# Sheet1.net
KiCad netlist of a schematic drawn in Altium Designer
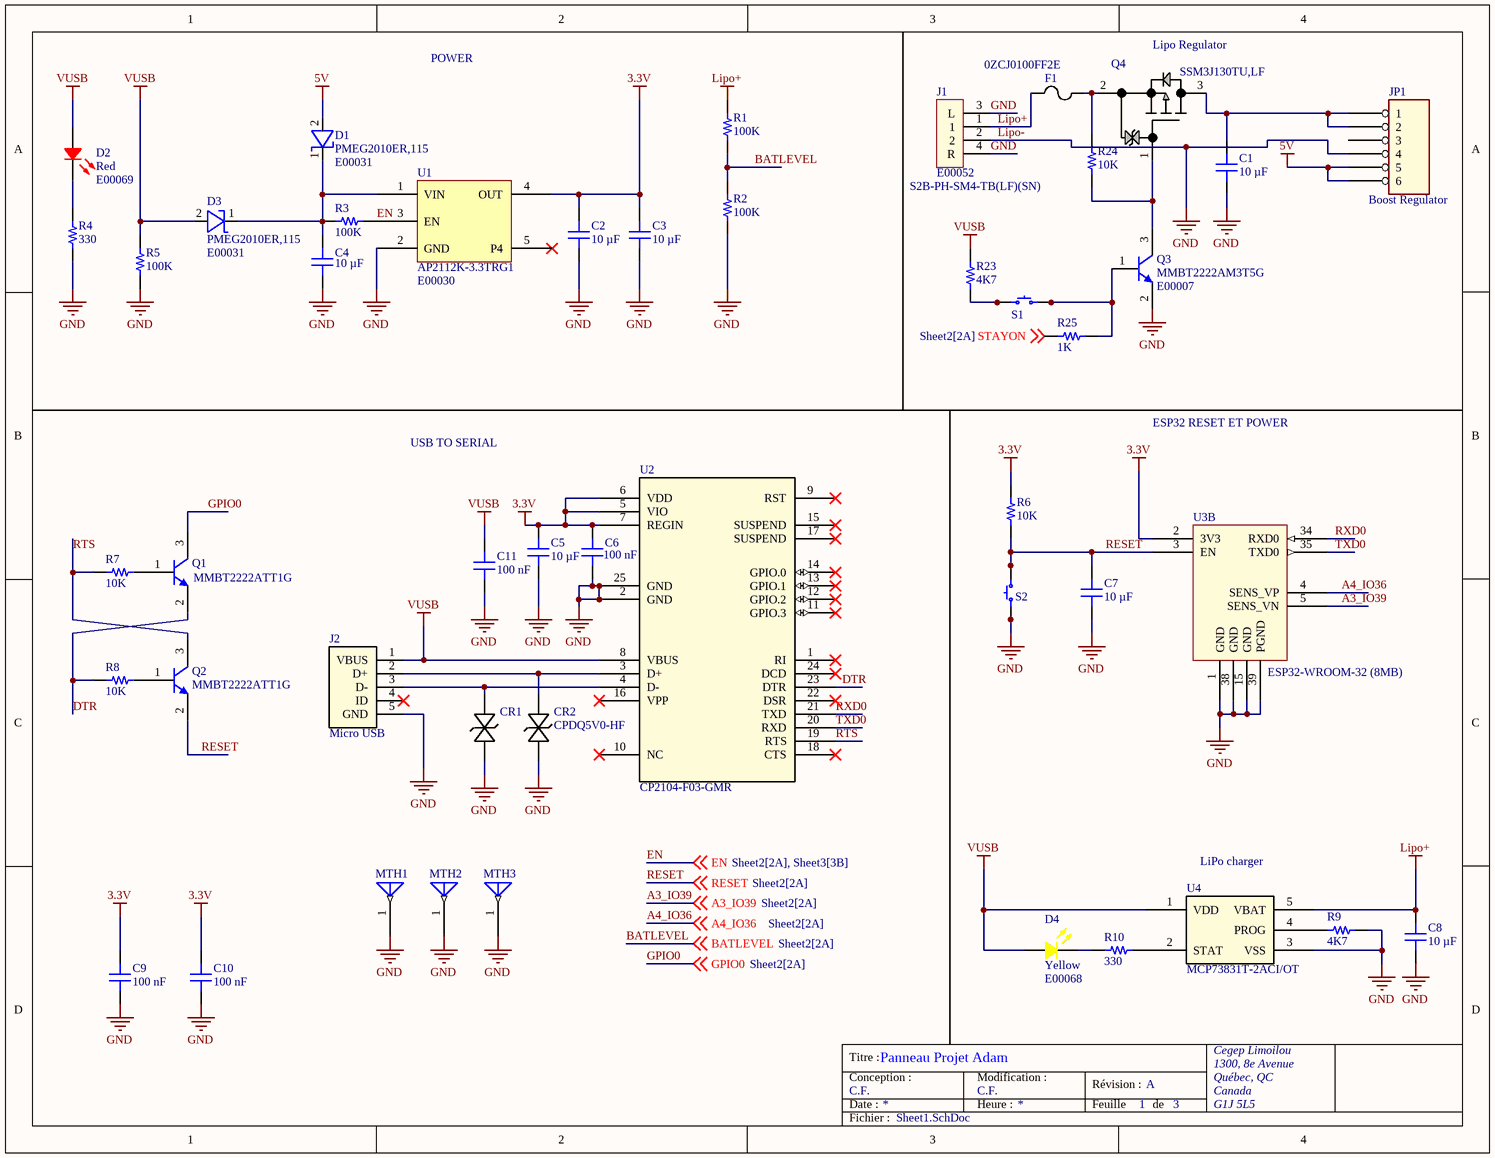
[diagram p0: Sheet1.SchDoc]

(export (version "E")
  (design (tool "Eeschema 10.0.6"))
  (components
    (comp (ref "C1")
      (value "10 µF")
      (footprint "CAP 0603")
      (description "CAP CER 10UF 10V X6S 0603")
      (fields
        (field (name "PART NUMBER") "GRM188C81A106MA73D")
        (field (name "MANUFACTURER") "Murata Electronics")
      )
      (libsource (lib "Celestial Altium Library - altium_library") (part "Capacitor"))
    )
    (comp (ref "C2")
      (value "10 µF")
      (footprint "CAP 0603")
      (description "CAP CER 10UF 10V X6S 0603")
      (fields
        (field (name "PART NUMBER") "GRM188C81A106MA73D")
        (field (name "MANUFACTURER") "Murata Electronics")
      )
      (libsource (lib "Celestial Altium Library - altium_library") (part "Capacitor"))
    )
    (comp (ref "C3")
      (value "10 µF")
      (footprint "CAP 0603")
      (description "CAP CER 10UF 10V X6S 0603")
      (fields
        (field (name "PART NUMBER") "GRM188C81A106MA73D")
        (field (name "MANUFACTURER") "Murata Electronics")
      )
      (libsource (lib "Celestial Altium Library - altium_library") (part "Capacitor"))
    )
    (comp (ref "C4")
      (value "10 µF")
      (footprint "CAP 0603")
      (description "CAP CER 10UF 10V X6S 0603")
      (fields
        (field (name "PART NUMBER") "GRM188C81A106MA73D")
        (field (name "MANUFACTURER") "Murata Electronics")
      )
      (libsource (lib "Celestial Altium Library - altium_library") (part "Capacitor"))
    )
    (comp (ref "C5")
      (value "10 µF")
      (footprint "CAP 0603")
      (description "CAP CER 10UF 10V X6S 0603")
      (fields
        (field (name "PART NUMBER") "GRM188C81A106MA73D")
        (field (name "MANUFACTURER") "Murata Electronics")
      )
      (libsource (lib "Celestial Altium Library - altium_library") (part "Capacitor"))
    )
    (comp (ref "C6")
      (value "100 nF")
      (footprint "CAP 0603")
      (description "CAP CER 10UF 10V X6S 0603")
      (fields
        (field (name "PART NUMBER") "GRM188C81A106MA73D")
        (field (name "MANUFACTURER") "Murata Electronics")
      )
      (libsource (lib "Celestial Altium Library - altium_library") (part "Capacitor"))
    )
    (comp (ref "C7")
      (value "10 µF")
      (footprint "CAP 0603")
      (description "CAP CER 10UF 10V X6S 0603")
      (fields
        (field (name "PART NUMBER") "GRM188C81A106MA73D")
        (field (name "MANUFACTURER") "Murata Electronics")
      )
      (libsource (lib "Celestial Altium Library - altium_library") (part "Capacitor"))
    )
    (comp (ref "C8")
      (value "10 µF")
      (footprint "CAP 0603")
      (description "CAP CER 10UF 10V X6S 0603")
      (fields
        (field (name "PART NUMBER") "GRM188C81A106MA73D")
        (field (name "MANUFACTURER") "Murata Electronics")
      )
      (libsource (lib "Celestial Altium Library - altium_library") (part "Capacitor"))
    )
    (comp (ref "C9")
      (value "100 nF")
      (footprint "CAP 0603")
      (description "CAP CER 10UF 10V X6S 0603")
      (fields
        (field (name "PART NUMBER") "GRM188C81A106MA73D")
        (field (name "MANUFACTURER") "Murata Electronics")
      )
      (libsource (lib "Celestial Altium Library - altium_library") (part "Capacitor"))
    )
    (comp (ref "C10")
      (value "100 nF")
      (footprint "CAP 0603")
      (description "CAP CER 10UF 10V X6S 0603")
      (fields
        (field (name "PART NUMBER") "GRM188C81A106MA73D")
        (field (name "MANUFACTURER") "Murata Electronics")
      )
      (libsource (lib "Celestial Altium Library - altium_library") (part "Capacitor"))
    )
    (comp (ref "C11")
      (value "100 nF")
      (footprint "CAP 0603")
      (description "CAP CER 10UF 10V X6S 0603")
      (fields
        (field (name "PART NUMBER") "GRM188C81A106MA73D")
        (field (name "MANUFACTURER") "Murata Electronics")
      )
      (libsource (lib "Celestial Altium Library - altium_library") (part "Capacitor"))
    )
    (comp (ref "CR1")
      (value "CPDQ5V0-HF")
      (footprint "CPDQ-M")
      (description "Diode TVS bidirectionnel")
      (libsource (lib "ADAM LIBRARY") (part "CPDQ5V0-HF"))
    )
    (comp (ref "CR2")
      (value "CPDQ5V0-HF")
      (footprint "CPDQ-M")
      (description "Diode TVS bidirectionnel")
      (libsource (lib "ADAM LIBRARY") (part "CPDQ5V0-HF"))
    )
    (comp (ref "D1")
      (value "PMEG2010ER,115")
      (footprint "DIODE_PMEG2010ER,115_NEX")
      (description "Diode shotkey")
      (fields (field (name "ADAM INVENTORY NUMBER 1") "E00031"))
      (libsource (lib "ADAM LIBRARY") (part "PMEG2010ER,115"))
    )
    (comp (ref "D2")
      (value "Red")
      (footprint "Red Led 0603")
      (description "0603 RED LED")
      (fields
        (field (name "MANUFACTURER") "American Bright Optoelectronics Corporation")
        (field (name "ADAM INVENTORY NUMBER 1") "E00069")
      )
      (libsource (lib "ADAM LIBRARY") (part "0603 RED LED"))
    )
    (comp (ref "D3")
      (value "PMEG2010ER,115")
      (footprint "DIODE_PMEG2010ER,115_NEX")
      (description "Diode shotkey")
      (fields (field (name "ADAM INVENTORY NUMBER 1") "E00031"))
      (libsource (lib "ADAM LIBRARY") (part "PMEG2010ER,115"))
    )
    (comp (ref "D4")
      (value "Yellow")
      (footprint "YELLOW LED 0603 - duplicate")
      (description "0603 YELLOW")
      (fields
        (field (name "MANUFACTURER") "American Bright Optoelectronics Corporation")
        (field (name "ADAM INVENTORY NUMBER 1") "E00068")
      )
      (libsource (lib "ADAM LIBRARY") (part "0603 YELLOW LED"))
    )
    (comp (ref "F1")
      (value "0ZCJ0100FF2E")
      (footprint "Fuse 500mA 0.6mm")
      (description "No Description Available")
      (libsource (lib "ADAM LIBRARY") (part "NANOSMDCH030F/24-02"))
    )
    (comp (ref "J1")
      (value "CONN JST 2P SM 90DEG")
      (footprint "S2B-PH-SM4-TB_LF__SN")
      (description "CONN SM JST 2P")
      (fields
        (field (name "ADAM INVENTORY NUMBER 1") "E00052")
        (field (name "SUPPLIER PART NUMBER 1") "S2B-PH-SM4-TB(LF)(SN)")
        (field (name "COPYRIGHT") "Copyright (C) 2023 Ultra Librarian. All rights reserved.")
      )
      (libsource (lib "ADAM LIBRARY") (part "CONN JST 2P SM 90DEG"))
    )
    (comp (ref "J2")
      (value "Micro USB")
      (footprint "CONN_1050170001_MOL")
      (description "No Description Available")
      (fields (field (name "COPYRIGHT") "Copyright (C) 2023 Ultra Librarian. All rights reserved."))
      (libsource (lib "Pannel") (part "1050170001"))
    )
    (comp (ref "JP1")
      (value "Boost Regulator")
      (footprint "HDR1X6")
      (libsource (lib "PCBDEV_Library") (part "HEADER 6"))
    )
    (comp (ref "MTH1")
      (value "NTENNA")
      (footprint "Mounting Hole")
      (libsource (lib "PCBDEV_Library") (part "ANTENNA"))
    )
    (comp (ref "MTH2")
      (value "ANTENNA")
      (footprint "Mounting Hole")
      (libsource (lib "PCBDEV_Library") (part "ANTENNA"))
    )
    (comp (ref "MTH3")
      (value "ANTENNA")
      (footprint "Mounting Hole")
      (libsource (lib "PCBDEV_Library") (part "ANTENNA"))
    )
    (comp (ref "Q1")
      (value "MMBT2222ATT1G")
      (footprint "SOT-416_1P65X0P9_ONS-M")
      (description "TRANS NPN 40V 0.6A SC75-3")
      (fields (field (name "MANUFACTURER") "ON Semiconductor"))
      (libsource (lib "Celestial Altium Library - altium_library") (part "ON SEMI NPN SC-75"))
    )
    (comp (ref "Q2")
      (value "MMBT2222ATT1G")
      (footprint "SOT-416_1P65X0P9_ONS-M")
      (description "TRANS NPN 40V 0.6A SC75-3")
      (fields (field (name "MANUFACTURER") "ON Semiconductor"))
      (libsource (lib "Celestial Altium Library - altium_library") (part "ON SEMI NPN SC-75"))
    )
    (comp (ref "Q3")
      (value "MMBT2222AM3T5G")
      (footprint "SOT_4C-E3-08_VIS-M")
      (description "TRANS NPN 40V 0.6A SOT-723")
      (fields
        (field (name "MANUFACTURER") "ON Semiconductor")
        (field (name "ADAM INVENTORY NUMBER 1") "E00007")
      )
      (libsource (lib "ADAM LIBRARY") (part "TRANS NPN 40V"))
    )
    (comp (ref "Q4")
      (value "SSM3J130TU,LF")
      (footprint "UFM_TOS")
      (description "No Description Available")
      (libsource (lib "ADAM LIBRARY") (part "SSM3J130TU,LF"))
    )
    (comp (ref "R1")
      (value "100K")
      (footprint "RES 0603")
      (description "RES SMD 100K OHM 0.1% 1/16W 0603")
      (fields
        (field (name "PART NUMBER") "CPF0603B100KE")
        (field (name "MANUFACTURER") "TE Connectivity Passive Product")
      )
      (libsource (lib "Celestial Altium Library - altium_library") (part "Resistor"))
    )
    (comp (ref "R2")
      (value "100K")
      (footprint "RES 0603")
      (description "RES SMD 100K OHM 0.1% 1/16W 0603")
      (fields
        (field (name "PART NUMBER") "CPF0603B100KE")
        (field (name "MANUFACTURER") "TE Connectivity Passive Product")
      )
      (libsource (lib "Celestial Altium Library - altium_library") (part "Resistor"))
    )
    (comp (ref "R3")
      (value "100K")
      (footprint "RES 0603")
      (description "RES SMD 100K OHM 0.1% 1/16W 0603")
      (fields
        (field (name "PART NUMBER") "CPF0603B100KE")
        (field (name "MANUFACTURER") "TE Connectivity Passive Product")
      )
      (libsource (lib "Celestial Altium Library - altium_library") (part "Resistor"))
    )
    (comp (ref "R4")
      (value "330")
      (footprint "RES 0603")
      (description "RES SMD 1K OHM 0.1% 1/16W 0603")
      (fields
        (field (name "PART NUMBER") "CPF0603B1K0E")
        (field (name "MANUFACTURER") "TE Connectivity Passive Product")
      )
      (libsource (lib "Celestial Altium Library - altium_library") (part "Resistor"))
    )
    (comp (ref "R5")
      (value "100K")
      (footprint "RES 0603")
      (description "RES SMD 100K OHM 0.1% 1/16W 0603")
      (fields
        (field (name "PART NUMBER") "CPF0603B100KE")
        (field (name "MANUFACTURER") "TE Connectivity Passive Product")
      )
      (libsource (lib "Celestial Altium Library - altium_library") (part "Resistor"))
    )
    (comp (ref "R6")
      (value "10K")
      (footprint "RES 0603")
      (description "RES 10K OHM 0.1% 1/16W 0603")
      (fields
        (field (name "PART NUMBER") "RNCS0603BKE10K0")
        (field (name "MANUFACTURER") "Stackpole Electronics Inc")
      )
      (libsource (lib "Celestial Altium Library - altium_library") (part "Resistor"))
    )
    (comp (ref "R7")
      (value "10K")
      (footprint "RES 0603")
      (description "RES 10K OHM 0.1% 1/16W 0603")
      (fields
        (field (name "PART NUMBER") "RNCS0603BKE10K0")
        (field (name "MANUFACTURER") "Stackpole Electronics Inc")
      )
      (libsource (lib "Celestial Altium Library - altium_library") (part "Resistor"))
    )
    (comp (ref "R8")
      (value "10K")
      (footprint "RES 0603")
      (description "RES 10K OHM 0.1% 1/16W 0603")
      (fields
        (field (name "PART NUMBER") "RNCS0603BKE10K0")
        (field (name "MANUFACTURER") "Stackpole Electronics Inc")
      )
      (libsource (lib "Celestial Altium Library - altium_library") (part "Resistor"))
    )
    (comp (ref "R9")
      (value "4K7")
      (footprint "RES 0603")
      (description "RES SMD 4.7K OHM 1% 1/10W 0603")
      (fields (field (name "PART NUMBER") "RT0603FRE074K7L") (field (name "MANUFACTURER") "Yageo"))
      (libsource (lib "Celestial Altium Library - altium_library") (part "Resistor"))
    )
    (comp (ref "R10")
      (value "330")
      (footprint "RES 0603")
      (description "RES SMD 1K OHM 0.1% 1/16W 0603")
      (fields
        (field (name "PART NUMBER") "CPF0603B1K0E")
        (field (name "MANUFACTURER") "TE Connectivity Passive Product")
      )
      (libsource (lib "Celestial Altium Library - altium_library") (part "Resistor"))
    )
    (comp (ref "R23")
      (value "4K7")
      (footprint "RES 0603")
      (description "RES SMD 100K OHM 0.1% 1/16W 0603")
      (fields
        (field (name "PART NUMBER") "CPF0603B100KE")
        (field (name "MANUFACTURER") "TE Connectivity Passive Product")
      )
      (libsource (lib "Celestial Altium Library - altium_library") (part "Resistor"))
    )
    (comp (ref "R24")
      (value "10K")
      (footprint "RES 0603")
      (description "RES SMD 100K OHM 0.1% 1/16W 0603")
      (fields
        (field (name "PART NUMBER") "CPF0603B100KE")
        (field (name "MANUFACTURER") "TE Connectivity Passive Product")
      )
      (libsource (lib "Celestial Altium Library - altium_library") (part "Resistor"))
    )
    (comp (ref "R25")
      (value "1K")
      (footprint "RES 0603")
      (description "RES SMD 100K OHM 0.1% 1/16W 0603")
      (fields
        (field (name "PART NUMBER") "CPF0603B100KE")
        (field (name "MANUFACTURER") "TE Connectivity Passive Product")
      )
      (libsource (lib "Celestial Altium Library - altium_library") (part "Resistor"))
    )
    (comp (ref "S1")
      (value "KMR741NG ULC LFS")
      (footprint "Switch Lin SMD")
      (description "SWITCH TACTILE SPST-NO 50MA 32V")
      (fields (field (name "MANUFACTURER") "C&K"))
      (libsource (lib "Celestial Altium Library - altium_library") (part "SPST-NO 4 PIN"))
    )
    (comp (ref "S2")
      (value "KMR741NG ULC LFS")
      (footprint "Switch Lin SMD")
      (description "SWITCH TACTILE SPST-NO 50MA 32V")
      (fields (field (name "MANUFACTURER") "C&K"))
      (libsource (lib "Celestial Altium Library - altium_library") (part "SPST-NO 4 PIN"))
    )
    (comp (ref "U1")
      (value "AP2112K-3.3TRG1")
      (footprint "AP2112R5-3.3TRG1_DIO")
      (description "REG LINEAIRE 3.3V")
      (fields (field (name "ADAM INVENTORY NUMBER 1") "E00030"))
      (libsource (lib "ADAM LIBRARY") (part "REG LIN 3.3V"))
    )
    (comp (ref "U2")
      (value "CP2104-F03-GMR")
      (footprint "QFN_F03-GMR_SIL-M")
      (description "No Description Available")
      (fields (field (name "COPYRIGHT") "Copyright (C) 2023 Ultra Librarian. All rights reserved."))
      (libsource (lib "Pannel") (part "CP2104-F03-GMR"))
    )
    (comp (ref "U3")
      (value "ESP32-WROOM-32 (8MB)")
      (footprint "ESP32-WROOM-32D")
      (description "No Description Available")
      (fields (field (name "COPYRIGHT") "Copyright (C) 2023 Ultra Librarian. All rights reserved."))
      (libsource (lib "ESP32-WROOM-32_8MB_") (part "ESP32-WROOM-32 (8MB)"))
    )
    (comp (ref "U4")
      (value "MCP73831T-2ACI/OT")
      (footprint "SOT23_MCP73831T-2ACI/OT_HNW")
      (description "No Description Available")
      (fields (field (name "COPYRIGHT") "Copyright (C) 2023 Ultra Librarian. All rights reserved."))
      (libsource (lib "Pannel") (part "MCP73831T-2ACI/OT"))
    )
  )
  (nets
    (net (code "1") (name "/DTR") (class "Default")
      (node (ref "Q1") (pin "2") (pinfunction "E_2") (pintype "passive"))
      (node (ref "R8") (pin "2") (pinfunction "2_2") (pintype "passive"))
      (node (ref "U2") (pin "23") (pinfunction "DTR_23") (pintype "passive"))
    )
    (net (code "2") (name "/RTS") (class "Default")
      (node (ref "Q2") (pin "3") (pinfunction "C_3") (pintype "passive"))
      (node (ref "R7") (pin "2") (pinfunction "2_2") (pintype "passive"))
      (node (ref "U2") (pin "19") (pinfunction "RTS_19") (pintype "passive"))
    )
    (net (code "3") (name "/RXD0") (class "Default")
      (node (ref "U2") (pin "21") (pinfunction "TXD_21") (pintype "passive"))
      (node (ref "U3") (pin "34") (pinfunction "RXD0_34") (pintype "input"))
    )
    (net (code "4") (name "/TXD0") (class "Default")
      (node (ref "U2") (pin "20") (pinfunction "RXD_20") (pintype "passive"))
      (node (ref "U3") (pin "35") (pinfunction "TXD0_35") (pintype "output"))
    )
    (net (code "5") (name "3.3V") (class "Default")
      (node (ref "C10") (pin "2") (pinfunction "2_2") (pintype "passive"))
      (node (ref "C2") (pin "2") (pinfunction "2_2") (pintype "passive"))
      (node (ref "C3") (pin "2") (pinfunction "2_2") (pintype "passive"))
      (node (ref "C5") (pin "2") (pinfunction "2_2") (pintype "passive"))
      (node (ref "C6") (pin "2") (pinfunction "2_2") (pintype "passive"))
      (node (ref "C9") (pin "2") (pinfunction "2_2") (pintype "passive"))
      (node (ref "R6") (pin "2") (pinfunction "2_2") (pintype "passive"))
      (node (ref "U1") (pin "4") (pinfunction "OUT_4") (pintype "passive"))
      (node (ref "U2") (pin "5") (pinfunction "VIO_5") (pintype "passive"))
      (node (ref "U2") (pin "6") (pinfunction "VDD_6") (pintype "power_in"))
      (node (ref "U2") (pin "7") (pinfunction "REGIN_7") (pintype "passive"))
      (node (ref "U3") (pin "2") (pinfunction "3V3_2") (pintype "power_in"))
    )
    (net (code "6") (name "5V") (class "Default")
      (node (ref "D1") (pin "2") (pinfunction "A_2") (pintype "passive"))
      (node (ref "JP1") (pin "5") (pinfunction "5_5") (pintype "passive"))
      (node (ref "JP1") (pin "6") (pinfunction "6_6") (pintype "passive"))
    )
    (net (code "7") (name "A3_IO39") (class "Default")
      (node (ref "U3") (pin "5") (pinfunction "SENS_VN_5") (pintype "passive"))
    )
    (net (code "8") (name "A4_IO36") (class "Default")
      (node (ref "U3") (pin "4") (pinfunction "SENS_VP_4") (pintype "passive"))
    )
    (net (code "9") (name "BATLEVEL") (class "Default")
      (node (ref "R1") (pin "1") (pinfunction "1_1") (pintype "passive"))
      (node (ref "R2") (pin "2") (pinfunction "2_2") (pintype "passive"))
    )
    (net (code "10") (name "EN") (class "Default")
      (node (ref "R3") (pin "1") (pinfunction "1_1") (pintype "passive"))
      (node (ref "U1") (pin "3") (pinfunction "EN_3") (pintype "passive"))
    )
    (net (code "11") (name "GND") (class "Default")
      (node (ref "C1") (pin "1") (pinfunction "1_1") (pintype "passive"))
      (node (ref "C10") (pin "1") (pinfunction "1_1") (pintype "passive"))
      (node (ref "C11") (pin "1") (pinfunction "1_1") (pintype "passive"))
      (node (ref "C2") (pin "1") (pinfunction "1_1") (pintype "passive"))
      (node (ref "C3") (pin "1") (pinfunction "1_1") (pintype "passive"))
      (node (ref "C4") (pin "1") (pinfunction "1_1") (pintype "passive"))
      (node (ref "C5") (pin "1") (pinfunction "1_1") (pintype "passive"))
      (node (ref "C6") (pin "1") (pinfunction "1_1") (pintype "passive"))
      (node (ref "C7") (pin "1") (pinfunction "1_1") (pintype "passive"))
      (node (ref "C8") (pin "1") (pinfunction "1_1") (pintype "passive"))
      (node (ref "C9") (pin "1") (pinfunction "1_1") (pintype "passive"))
      (node (ref "CR1") (pin "1") (pinfunction "1_1") (pintype "passive"))
      (node (ref "CR2") (pin "1") (pinfunction "1_1") (pintype "passive"))
      (node (ref "J1") (pin "2") (pinfunction "2_2") (pintype "passive"))
      (node (ref "J1") (pin "3") (pinfunction "L_3") (pintype "passive"))
      (node (ref "J1") (pin "4") (pinfunction "R_4") (pintype "passive"))
      (node (ref "J2") (pin "5") (pinfunction "GND_5") (pintype "passive"))
      (node (ref "JP1") (pin "4") (pinfunction "4_4") (pintype "passive"))
      (node (ref "MTH1") (pin "1") (pinfunction "1_1") (pintype "output"))
      (node (ref "MTH2") (pin "1") (pinfunction "1_1") (pintype "output"))
      (node (ref "MTH3") (pin "1") (pinfunction "1_1") (pintype "output"))
      (node (ref "Q3") (pin "2") (pinfunction "E_2") (pintype "passive"))
      (node (ref "R2") (pin "1") (pinfunction "1_1") (pintype "passive"))
      (node (ref "R4") (pin "2") (pinfunction "2_2") (pintype "passive"))
      (node (ref "R5") (pin "1") (pinfunction "1_1") (pintype "passive"))
      (node (ref "R9") (pin "2") (pinfunction "2_2") (pintype "passive"))
      (node (ref "S2") (pin "1") (pinfunction "1_1") (pintype "passive"))
      (node (ref "S2") (pin "2") (pinfunction "2_2") (pintype "passive"))
      (node (ref "U1") (pin "2") (pinfunction "GND_2") (pintype "passive"))
      (node (ref "U2") (pin "2") (pinfunction "GND_2") (pintype "passive"))
      (node (ref "U2") (pin "25") (pinfunction "GND_25") (pintype "passive"))
      (node (ref "U3") (pin "1") (pinfunction "GND_1") (pintype "power_in"))
      (node (ref "U3") (pin "15") (pinfunction "GND_15") (pintype "power_in"))
      (node (ref "U3") (pin "38") (pinfunction "GND_38") (pintype "power_in"))
      (node (ref "U3") (pin "39") (pinfunction "PGND_39") (pintype "power_in"))
      (node (ref "U4") (pin "3") (pinfunction "VSS_3") (pintype "passive"))
    )
    (net (code "12") (name "GPIO0") (class "Default")
      (node (ref "Q1") (pin "3") (pinfunction "C_3") (pintype "passive"))
    )
    (net (code "13") (name "Lipo+") (class "Default")
      (node (ref "C8") (pin "2") (pinfunction "2_2") (pintype "passive"))
      (node (ref "F1") (pin "1") (pinfunction "1_1") (pintype "passive"))
      (node (ref "J1") (pin "1") (pinfunction "1_1") (pintype "passive"))
      (node (ref "R1") (pin "2") (pinfunction "2_2") (pintype "passive"))
      (node (ref "U4") (pin "5") (pinfunction "VBAT_5") (pintype "passive"))
    )
    (net (code "14") (name "Net-(C1-Pad2)") (class "Default")
      (node (ref "C1") (pin "2") (pinfunction "2_2") (pintype "passive"))
      (node (ref "JP1") (pin "1") (pinfunction "1_1") (pintype "passive"))
      (node (ref "JP1") (pin "2") (pinfunction "2_2") (pintype "passive"))
      (node (ref "Q4") (pin "3") (pinfunction "3_3") (pintype "passive"))
    )
    (net (code "15") (name "Net-(D1-K)") (class "Default")
      (node (ref "C4") (pin "2") (pinfunction "2_2") (pintype "passive"))
      (node (ref "D1") (pin "1") (pinfunction "K_1") (pintype "passive"))
      (node (ref "D3") (pin "1") (pinfunction "K_1") (pintype "passive"))
      (node (ref "R3") (pin "2") (pinfunction "2_2") (pintype "passive"))
      (node (ref "U1") (pin "1") (pinfunction "VIN_1") (pintype "passive"))
    )
    (net (code "16") (name "Net-(D2-Pad2)") (class "Default")
      (node (ref "D2") (pin "2") (pinfunction "2_2") (pintype "passive"))
      (node (ref "R4") (pin "1") (pinfunction "1_1") (pintype "passive"))
    )
    (net (code "17") (name "Net-(D4-Pad2)") (class "Default")
      (node (ref "D4") (pin "2") (pinfunction "2_2") (pintype "passive"))
      (node (ref "R10") (pin "1") (pinfunction "1_1") (pintype "passive"))
    )
    (net (code "18") (name "Net-(F1-Pad2)") (class "Default")
      (node (ref "F1") (pin "2") (pinfunction "2_2") (pintype "passive"))
      (node (ref "Q4") (pin "2") (pinfunction "2_2") (pintype "passive"))
      (node (ref "R24") (pin "2") (pinfunction "2_2") (pintype "passive"))
    )
    (net (code "19") (name "Net-(J2-D+)") (class "Default")
      (node (ref "CR2") (pin "2") (pinfunction "2_2") (pintype "passive"))
      (node (ref "J2") (pin "2") (pinfunction "D+_2") (pintype "passive"))
      (node (ref "U2") (pin "3") (pinfunction "D+_3") (pintype "passive"))
    )
    (net (code "20") (name "Net-(J2-D-)") (class "Default")
      (node (ref "CR1") (pin "2") (pinfunction "2_2") (pintype "passive"))
      (node (ref "J2") (pin "3") (pinfunction "D-_3") (pintype "passive"))
      (node (ref "U2") (pin "4") (pinfunction "D-_4") (pintype "passive"))
    )
    (net (code "21") (name "Net-(Q1-B)") (class "Default")
      (node (ref "Q1") (pin "1") (pinfunction "B_1") (pintype "passive"))
      (node (ref "R7") (pin "1") (pinfunction "1_1") (pintype "passive"))
    )
    (net (code "22") (name "Net-(Q2-B)") (class "Default")
      (node (ref "Q2") (pin "1") (pinfunction "B_1") (pintype "passive"))
      (node (ref "R8") (pin "1") (pinfunction "1_1") (pintype "passive"))
    )
    (net (code "23") (name "Net-(Q3-B)") (class "Default")
      (node (ref "Q3") (pin "1") (pinfunction "B_1") (pintype "passive"))
      (node (ref "R25") (pin "1") (pinfunction "1_1") (pintype "passive"))
      (node (ref "S1") (pin "3") (pinfunction "3_3") (pintype "passive"))
      (node (ref "S1") (pin "4") (pinfunction "4_4") (pintype "passive"))
    )
    (net (code "24") (name "Net-(Q3-C)") (class "Default")
      (node (ref "Q3") (pin "3") (pinfunction "C_3") (pintype "passive"))
      (node (ref "Q4") (pin "1") (pinfunction "1_1") (pintype "passive"))
      (node (ref "R24") (pin "1") (pinfunction "1_1") (pintype "passive"))
    )
    (net (code "25") (name "Net-(R23-Pad1)") (class "Default")
      (node (ref "R23") (pin "1") (pinfunction "1_1") (pintype "passive"))
      (node (ref "S1") (pin "1") (pinfunction "1_1") (pintype "passive"))
      (node (ref "S1") (pin "2") (pinfunction "2_2") (pintype "passive"))
    )
    (net (code "26") (name "Net-(U4-PROG)") (class "Default")
      (node (ref "R9") (pin "1") (pinfunction "1_1") (pintype "passive"))
      (node (ref "U4") (pin "4") (pinfunction "PROG_4") (pintype "passive"))
    )
    (net (code "27") (name "Net-(U4-STAT)") (class "Default")
      (node (ref "R10") (pin "2") (pinfunction "2_2") (pintype "passive"))
      (node (ref "U4") (pin "2") (pinfunction "STAT_2") (pintype "passive"))
    )
    (net (code "28") (name "RESET") (class "Default")
      (node (ref "C7") (pin "2") (pinfunction "2_2") (pintype "passive"))
      (node (ref "Q2") (pin "2") (pinfunction "E_2") (pintype "passive"))
      (node (ref "R6") (pin "1") (pinfunction "1_1") (pintype "passive"))
      (node (ref "S2") (pin "3") (pinfunction "3_3") (pintype "passive"))
      (node (ref "S2") (pin "4") (pinfunction "4_4") (pintype "passive"))
      (node (ref "U3") (pin "3") (pinfunction "EN_3") (pintype "passive"))
    )
    (net (code "29") (name "STAYON") (class "Default")
      (node (ref "R25") (pin "2") (pinfunction "2_2") (pintype "passive"))
    )
    (net (code "30") (name "VUSB") (class "Default")
      (node (ref "C11") (pin "2") (pinfunction "2_2") (pintype "passive"))
      (node (ref "D2") (pin "1") (pinfunction "1_1") (pintype "passive"))
      (node (ref "D3") (pin "2") (pinfunction "A_2") (pintype "passive"))
      (node (ref "D4") (pin "1") (pinfunction "1_1") (pintype "passive"))
      (node (ref "J2") (pin "1") (pinfunction "VBUS_1") (pintype "passive"))
      (node (ref "R23") (pin "2") (pinfunction "2_2") (pintype "passive"))
      (node (ref "R5") (pin "2") (pinfunction "2_2") (pintype "passive"))
      (node (ref "U2") (pin "8") (pinfunction "VBUS_8") (pintype "passive"))
      (node (ref "U4") (pin "1") (pinfunction "VDD_1") (pintype "passive"))
    )
    (net (code "31") (name "unconnected-(J2-ID-Pad4)") (class "Default")
      (node (ref "J2") (pin "4") (pinfunction "ID_4") (pintype "passive+no_connect"))
    )
    (net (code "32") (name "unconnected-(JP1-Pad3)") (class "Default")
      (node (ref "JP1") (pin "3") (pinfunction "3_3") (pintype "passive"))
    )
    (net (code "33") (name "unconnected-(U1-P4-Pad5)") (class "Default")
      (node (ref "U1") (pin "5") (pinfunction "P4_5") (pintype "passive+no_connect"))
    )
    (net (code "34") (name "unconnected-(U2-CTS-Pad18)") (class "Default")
      (node (ref "U2") (pin "18") (pinfunction "CTS_18") (pintype "passive+no_connect"))
    )
    (net (code "35") (name "unconnected-(U2-DCD-Pad24)") (class "Default")
      (node (ref "U2") (pin "24") (pinfunction "DCD_24") (pintype "passive+no_connect"))
    )
    (net (code "36") (name "unconnected-(U2-DSR-Pad22)") (class "Default")
      (node (ref "U2") (pin "22") (pinfunction "DSR_22") (pintype "passive+no_connect"))
    )
    (net (code "37") (name "unconnected-(U2-GPIO.0-Pad14)") (class "Default")
      (node (ref "U2") (pin "14") (pinfunction "GPIO.0_14") (pintype "bidirectional+no_connect"))
    )
    (net (code "38") (name "unconnected-(U2-GPIO.1-Pad13)") (class "Default")
      (node (ref "U2") (pin "13") (pinfunction "GPIO.1_13") (pintype "bidirectional+no_connect"))
    )
    (net (code "39") (name "unconnected-(U2-GPIO.2-Pad12)") (class "Default")
      (node (ref "U2") (pin "12") (pinfunction "GPIO.2_12") (pintype "bidirectional+no_connect"))
    )
    (net (code "40") (name "unconnected-(U2-GPIO.3-Pad11)") (class "Default")
      (node (ref "U2") (pin "11") (pinfunction "GPIO.3_11") (pintype "bidirectional+no_connect"))
    )
    (net (code "41") (name "unconnected-(U2-NC-Pad10)") (class "Default")
      (node (ref "U2") (pin "10") (pinfunction "NC_10") (pintype "passive+no_connect"))
    )
    (net (code "42") (name "unconnected-(U2-RI-Pad1)") (class "Default")
      (node (ref "U2") (pin "1") (pinfunction "RI_1") (pintype "passive+no_connect"))
    )
    (net (code "43") (name "unconnected-(U2-RST-Pad9)") (class "Default")
      (node (ref "U2") (pin "9") (pinfunction "RST_9") (pintype "passive+no_connect"))
    )
    (net (code "44") (name "unconnected-(U2-SUSPEND-Pad15)") (class "Default")
      (node (ref "U2") (pin "15") (pinfunction "SUSPEND_15") (pintype "passive+no_connect"))
    )
    (net (code "45") (name "unconnected-(U2-SUSPEND-Pad17)") (class "Default")
      (node (ref "U2") (pin "17") (pinfunction "SUSPEND_17") (pintype "passive+no_connect"))
    )
    (net (code "46") (name "unconnected-(U2-VPP-Pad16)") (class "Default")
      (node (ref "U2") (pin "16") (pinfunction "VPP_16") (pintype "power_in+no_connect"))
    )
  )
)
